# NRF24L01_DS18B20a.net
KiCad netlist of a schematic drawn in EAGLE
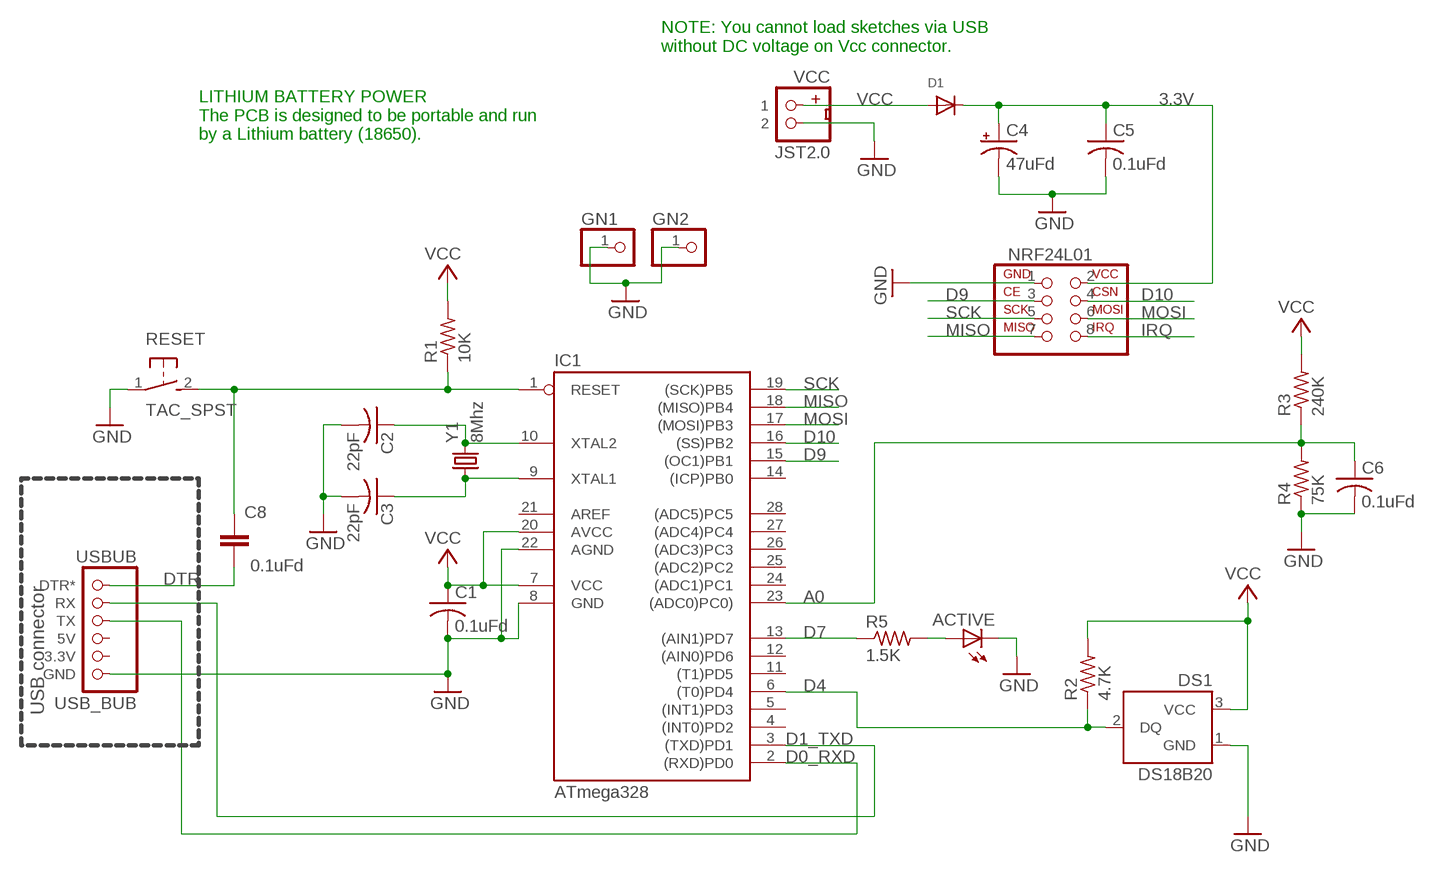
[diagram p0: schematic, sheet 1]

(export (version "E")
  (design (tool "Eeschema 10.0.6"))
  (components
    (comp (ref "ACTIVE")
      (value "LED3MM")
      (footprint "eagle-import:LED3MM")
      (libsource (lib "eagle-import") (part "LED3MM"))
    )
    (comp (ref "C1")
      (value "0.1uFd")
      (footprint "eagle-import:C025-025X050")
      (libsource (lib "eagle-import") (part "C-US025-025X050"))
    )
    (comp (ref "C2")
      (value "22pF")
      (footprint "eagle-import:C025-025X050")
      (libsource (lib "eagle-import") (part "C-US025-025X050"))
    )
    (comp (ref "C3")
      (value "22pF")
      (footprint "eagle-import:C025-025X050")
      (libsource (lib "eagle-import") (part "C-US025-025X050"))
    )
    (comp (ref "C4")
      (value "47uFd")
      (footprint "eagle-import:E2,5-6")
      (libsource (lib "eagle-import") (part "CPOL-USE2.5-6"))
    )
    (comp (ref "C5")
      (value "0.1uFd")
      (footprint "eagle-import:C025-025X050")
      (libsource (lib "eagle-import") (part "C-US025-025X050"))
    )
    (comp (ref "C6")
      (value "0.1uFd")
      (footprint "eagle-import:C025-025X050")
      (libsource (lib "eagle-import") (part "C-US025-025X050"))
    )
    (comp (ref "C8")
      (value "0.1uFd")
      (footprint "eagle-import:C050-025X075")
      (libsource (lib "eagle-import") (part "C-EU050-025X075"))
    )
    (comp (ref "D1")
      (value "DIODEDO-1N4148")
      (footprint "eagle-import:DO-1N4148")
      (libsource (lib "eagle-import") (part "DIODEDO-1N4148"))
    )
    (comp (ref "DS1")
      (value "DS18B20")
      (footprint "eagle-import:DS18B20")
      (libsource (lib "eagle-import") (part "DS18B20"))
    )
    (comp (ref "GN1")
      (value "PINHD-1X1")
      (footprint "eagle-import:1X01")
      (libsource (lib "eagle-import") (part "PINHD-1X1"))
    )
    (comp (ref "GN2")
      (value "PINHD-1X1")
      (footprint "eagle-import:1X01")
      (libsource (lib "eagle-import") (part "PINHD-1X1"))
    )
    (comp (ref "IC1")
      (value "ATmega328")
      (footprint "eagle-import:DIL28-3")
      (libsource (lib "eagle-import") (part "AT90S4433P"))
    )
    (comp (ref "NRF24L01")
      (value "NRF24L01+")
      (footprint "eagle-import:NRF24L01+")
      (libsource (lib "eagle-import") (part "NRF24L01+"))
    )
    (comp (ref "R1")
      (value "10K")
      (footprint "eagle-import:0207_2V")
      (libsource (lib "eagle-import") (part "R-US_0207/2V"))
    )
    (comp (ref "R2")
      (value "4.7K")
      (footprint "eagle-import:0207_2V")
      (libsource (lib "eagle-import") (part "R-US_0207/2V"))
    )
    (comp (ref "R3")
      (value "240K")
      (footprint "eagle-import:0207_10")
      (libsource (lib "eagle-import") (part "R-US_0207/10"))
    )
    (comp (ref "R4")
      (value "75K")
      (footprint "eagle-import:0207_2V")
      (libsource (lib "eagle-import") (part "R-US_0207/2V"))
    )
    (comp (ref "R5")
      (value "1.5K")
      (footprint "eagle-import:0207_2V")
      (libsource (lib "eagle-import") (part "R-US_0207/2V"))
    )
    (comp (ref "RESET")
      (value "TAC_SPST")
      (footprint "eagle-import:TACTILE-SPST")
      (libsource (lib "eagle-import") (part "TAC_SPST"))
    )
    (comp (ref "USBUB")
      (value "USB_BUB")
      (footprint "eagle-import:USB_BUB")
      (libsource (lib "eagle-import") (part "USB_BUB"))
    )
    (comp (ref "VCC")
      (value "JST2.0")
      (footprint "eagle-import:JST2.0")
      (libsource (lib "eagle-import") (part "JST2.0"))
    )
    (comp (ref "Y1")
      (value "8Mhz")
      (footprint "eagle-import:TC38H")
      (libsource (lib "eagle-import") (part "CRYSTALTC38H"))
    )
  )
  (nets
    (net (code "1") (name "/3.3V") (class "Default")
      (node (ref "C4") (pin "+") (pinfunction "+_+") (pintype "passive"))
      (node (ref "C5") (pin "1") (pinfunction "1_1") (pintype "passive"))
      (node (ref "D1") (pin "C") (pinfunction "C_C") (pintype "passive"))
      (node (ref "NRF24L01") (pin "2") (pinfunction "2_2") (pintype "passive"))
    )
    (net (code "2") (name "/A0") (class "Default")
      (node (ref "C6") (pin "1") (pinfunction "1_1") (pintype "passive"))
      (node (ref "IC1") (pin "23") (pinfunction "(ADC0)PC0)_23") (pintype "bidirectional"))
      (node (ref "R3") (pin "1") (pinfunction "1_1") (pintype "passive"))
      (node (ref "R4") (pin "2") (pinfunction "2_2") (pintype "passive"))
    )
    (net (code "3") (name "/D0_RXD") (class "Default")
      (node (ref "IC1") (pin "2") (pinfunction "(RXD)PD0_2") (pintype "bidirectional"))
      (node (ref "USBUB") (pin "TX") (pinfunction "TX_TX") (pintype "passive"))
    )
    (net (code "4") (name "/D1_TXD") (class "Default")
      (node (ref "IC1") (pin "3") (pinfunction "(TXD)PD1_3") (pintype "bidirectional"))
      (node (ref "USBUB") (pin "RX") (pinfunction "RX_RX") (pintype "passive"))
    )
    (net (code "5") (name "/D4") (class "Default")
      (node (ref "DS1") (pin "2") (pinfunction "DQ_2") (pintype "bidirectional"))
      (node (ref "IC1") (pin "6") (pinfunction "(T0)PD4_6") (pintype "bidirectional"))
      (node (ref "R2") (pin "1") (pinfunction "1_1") (pintype "passive"))
    )
    (net (code "6") (name "/D7") (class "Default")
      (node (ref "IC1") (pin "13") (pinfunction "(AIN1)PD7_13") (pintype "bidirectional"))
      (node (ref "R5") (pin "1") (pinfunction "1_1") (pintype "passive"))
    )
    (net (code "7") (name "/D9") (class "Default")
      (node (ref "IC1") (pin "15") (pinfunction "(OC1)PB1_15") (pintype "bidirectional"))
      (node (ref "NRF24L01") (pin "3") (pinfunction "3_3") (pintype "passive"))
    )
    (net (code "8") (name "/D10") (class "Default")
      (node (ref "IC1") (pin "16") (pinfunction "(SS)PB2_16") (pintype "bidirectional"))
      (node (ref "NRF24L01") (pin "4") (pinfunction "4_4") (pintype "passive"))
    )
    (net (code "9") (name "/DTR") (class "Default")
      (node (ref "C8") (pin "1") (pinfunction "1_1") (pintype "passive"))
      (node (ref "USBUB") (pin "DTR*") (pinfunction "DTR*_DTR*") (pintype "passive"))
    )
    (net (code "10") (name "/IRQ") (class "Default")
      (node (ref "NRF24L01") (pin "8") (pinfunction "8_8") (pintype "passive"))
    )
    (net (code "11") (name "/MISO") (class "Default")
      (node (ref "IC1") (pin "18") (pinfunction "(MISO)PB4_18") (pintype "bidirectional"))
      (node (ref "NRF24L01") (pin "7") (pinfunction "7_7") (pintype "passive"))
    )
    (net (code "12") (name "/MOSI") (class "Default")
      (node (ref "IC1") (pin "17") (pinfunction "(MOSI)PB3_17") (pintype "bidirectional"))
      (node (ref "NRF24L01") (pin "6") (pinfunction "6_6") (pintype "passive"))
    )
    (net (code "13") (name "/SCK") (class "Default")
      (node (ref "IC1") (pin "19") (pinfunction "(SCK)PB5_19") (pintype "bidirectional"))
      (node (ref "NRF24L01") (pin "5") (pinfunction "5_5") (pintype "passive"))
    )
    (net (code "14") (name "GND") (class "Default")
      (node (ref "ACTIVE") (pin "K") (pinfunction "C_K") (pintype "passive"))
      (node (ref "C1") (pin "2") (pinfunction "2_2") (pintype "passive"))
      (node (ref "C2") (pin "2") (pinfunction "2_2") (pintype "passive"))
      (node (ref "C3") (pin "2") (pinfunction "2_2") (pintype "passive"))
      (node (ref "C4") (pin "-") (pinfunction "-_-") (pintype "passive"))
      (node (ref "C5") (pin "2") (pinfunction "2_2") (pintype "passive"))
      (node (ref "C6") (pin "2") (pinfunction "2_2") (pintype "passive"))
      (node (ref "DS1") (pin "1") (pinfunction "GND_1") (pintype "bidirectional"))
      (node (ref "GN1") (pin "1") (pinfunction "1_1") (pintype "passive"))
      (node (ref "GN2") (pin "1") (pinfunction "1_1") (pintype "passive"))
      (node (ref "IC1") (pin "22") (pinfunction "AGND_22") (pintype "power_in"))
      (node (ref "IC1") (pin "8") (pinfunction "GND_8") (pintype "power_in"))
      (node (ref "NRF24L01") (pin "1") (pinfunction "1_1") (pintype "passive"))
      (node (ref "R4") (pin "1") (pinfunction "1_1") (pintype "passive"))
      (node (ref "RESET") (pin "1") (pinfunction "1_1") (pintype "passive"))
      (node (ref "USBUB") (pin "GND") (pinfunction "GND_GND") (pintype "passive"))
      (node (ref "VCC") (pin "2") (pinfunction "2_2") (pintype "passive"))
    )
    (net (code "15") (name "Net-(ACTIVE-PadA)") (class "Default")
      (node (ref "ACTIVE") (pin "A") (pinfunction "A_A") (pintype "passive"))
      (node (ref "R5") (pin "2") (pinfunction "2_2") (pintype "passive"))
    )
    (net (code "16") (name "Net-(IC1-RESET)") (class "Default")
      (node (ref "C8") (pin "2") (pinfunction "2_2") (pintype "passive"))
      (node (ref "IC1") (pin "1") (pinfunction "RESET_1") (pintype "input"))
      (node (ref "R1") (pin "1") (pinfunction "1_1") (pintype "passive"))
      (node (ref "RESET") (pin "2") (pinfunction "2_2") (pintype "passive"))
    )
    (net (code "17") (name "Net-(IC1-XTAL1)") (class "Default")
      (node (ref "C3") (pin "1") (pinfunction "1_1") (pintype "passive"))
      (node (ref "IC1") (pin "9") (pinfunction "XTAL1_9") (pintype "bidirectional"))
      (node (ref "Y1") (pin "1") (pinfunction "1_1") (pintype "passive"))
    )
    (net (code "18") (name "Net-(IC1-XTAL2)") (class "Default")
      (node (ref "C2") (pin "1") (pinfunction "1_1") (pintype "passive"))
      (node (ref "IC1") (pin "10") (pinfunction "XTAL2_10") (pintype "bidirectional"))
      (node (ref "Y1") (pin "2") (pinfunction "2_2") (pintype "passive"))
    )
    (net (code "19") (name "VCC") (class "Default")
      (node (ref "C1") (pin "1") (pinfunction "1_1") (pintype "passive"))
      (node (ref "D1") (pin "A") (pinfunction "A_A") (pintype "passive"))
      (node (ref "DS1") (pin "3") (pinfunction "VCC_3") (pintype "bidirectional"))
      (node (ref "IC1") (pin "20") (pinfunction "AVCC_20") (pintype "power_in"))
      (node (ref "IC1") (pin "7") (pinfunction "VCC_7") (pintype "power_in"))
      (node (ref "R1") (pin "2") (pinfunction "2_2") (pintype "passive"))
      (node (ref "R2") (pin "2") (pinfunction "2_2") (pintype "passive"))
      (node (ref "R3") (pin "2") (pinfunction "2_2") (pintype "passive"))
      (node (ref "VCC") (pin "1") (pinfunction "1_1") (pintype "passive"))
    )
    (net (code "20") (name "unconnected-(IC1-(ADC1)PC1-Pad24)") (class "Default")
      (node (ref "IC1") (pin "24") (pinfunction "(ADC1)PC1_24") (pintype "bidirectional"))
    )
    (net (code "21") (name "unconnected-(IC1-(ADC2)PC2-Pad25)") (class "Default")
      (node (ref "IC1") (pin "25") (pinfunction "(ADC2)PC2_25") (pintype "bidirectional"))
    )
    (net (code "22") (name "unconnected-(IC1-(ADC3)PC3-Pad26)") (class "Default")
      (node (ref "IC1") (pin "26") (pinfunction "(ADC3)PC3_26") (pintype "bidirectional"))
    )
    (net (code "23") (name "unconnected-(IC1-(ADC4)PC4-Pad27)") (class "Default")
      (node (ref "IC1") (pin "27") (pinfunction "(ADC4)PC4_27") (pintype "bidirectional"))
    )
    (net (code "24") (name "unconnected-(IC1-(ADC5)PC5-Pad28)") (class "Default")
      (node (ref "IC1") (pin "28") (pinfunction "(ADC5)PC5_28") (pintype "bidirectional"))
    )
    (net (code "25") (name "unconnected-(IC1-(AIN0)PD6-Pad12)") (class "Default")
      (node (ref "IC1") (pin "12") (pinfunction "(AIN0)PD6_12") (pintype "bidirectional"))
    )
    (net (code "26") (name "unconnected-(IC1-(ICP)PB0-Pad14)") (class "Default")
      (node (ref "IC1") (pin "14") (pinfunction "(ICP)PB0_14") (pintype "bidirectional"))
    )
    (net (code "27") (name "unconnected-(IC1-(INT0)PD2-Pad4)") (class "Default")
      (node (ref "IC1") (pin "4") (pinfunction "(INT0)PD2_4") (pintype "bidirectional"))
    )
    (net (code "28") (name "unconnected-(IC1-(INT1)PD3-Pad5)") (class "Default")
      (node (ref "IC1") (pin "5") (pinfunction "(INT1)PD3_5") (pintype "bidirectional"))
    )
    (net (code "29") (name "unconnected-(IC1-(T1)PD5-Pad11)") (class "Default")
      (node (ref "IC1") (pin "11") (pinfunction "(T1)PD5_11") (pintype "bidirectional"))
    )
    (net (code "30") (name "unconnected-(IC1-AREF-Pad21)") (class "Default")
      (node (ref "IC1") (pin "21") (pinfunction "AREF_21") (pintype "passive"))
    )
    (net (code "31") (name "unconnected-(USBUB-Pad3.3V)") (class "Default")
      (node (ref "USBUB") (pin "3.3V") (pinfunction "3.3V_3.3V") (pintype "passive"))
    )
    (net (code "32") (name "unconnected-(USBUB-Pad5V)") (class "Default")
      (node (ref "USBUB") (pin "5V") (pinfunction "5V_5V") (pintype "passive"))
    )
  )
)
